# FIT_FPGA_G-H.net
KiCad netlist of a schematic drawn in Altium Designer
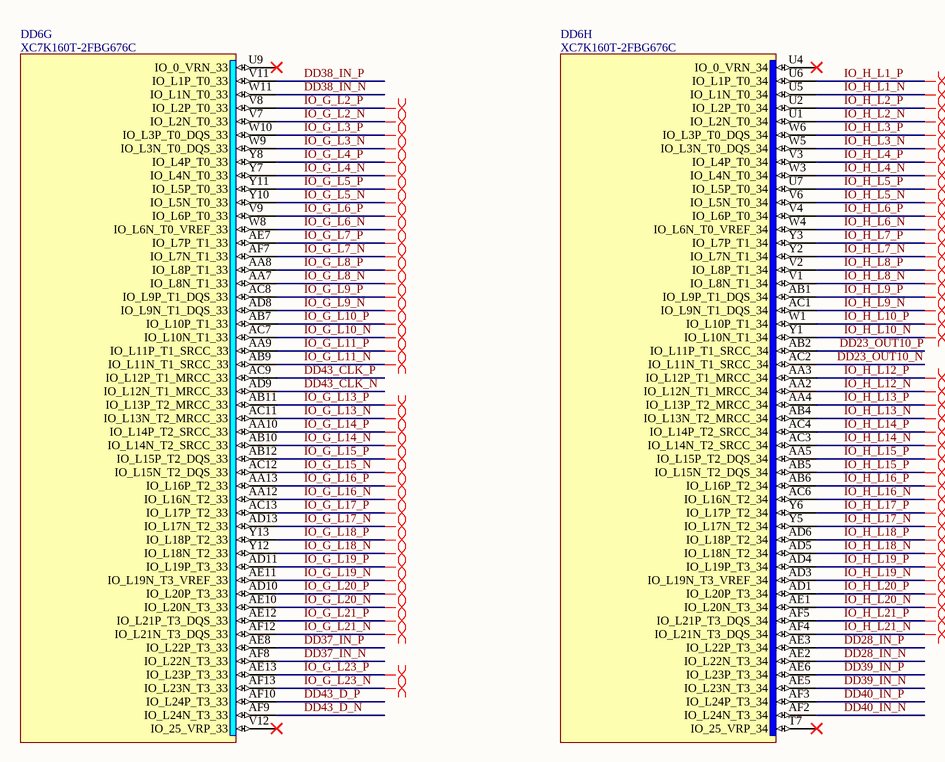
[diagram p0: FIT_FPGA_G-H.SchDoc]

(export (version "E")
  (design (tool "Eeschema 10.0.6"))
  (components
    (comp (ref "DD6")
      (value "XC7K160T-2FBG676C")
      (footprint "BGA676C100P26X26_2700X2700X254")
      (description "KINTEX-7, FPGA, 676-Ball BGA, Pb-Free")
      (fields (field (name "MANUFACTURER") "XILINX") (field (name "AUTHOR") "CERN DEM BC"))
      (libsource (lib "ICs And Semiconductors") (part "XC7K160T-xFBG676"))
    )
  )
  (nets
    (net (code "1") (name "/DD23_OUT10_N") (class "Default")
      (node (ref "DD6") (pin "AC2") (pinfunction "IO_L11N_T1_SRCC_34_AC2") (pintype "bidirectional"))
    )
    (net (code "2") (name "/DD23_OUT10_P") (class "Default")
      (node (ref "DD6") (pin "AB2") (pinfunction "IO_L11P_T1_SRCC_34_AB2") (pintype "bidirectional"))
    )
    (net (code "3") (name "/DD28_IN_N") (class "Default")
      (node (ref "DD6") (pin "AE2") (pinfunction "IO_L22N_T3_34_AE2") (pintype "bidirectional"))
    )
    (net (code "4") (name "/DD28_IN_P") (class "Default")
      (node (ref "DD6") (pin "AE3") (pinfunction "IO_L22P_T3_34_AE3") (pintype "bidirectional"))
    )
    (net (code "5") (name "/DD37_IN_N") (class "Default")
      (node (ref "DD6") (pin "AF8") (pinfunction "IO_L22N_T3_33_AF8") (pintype "bidirectional"))
    )
    (net (code "6") (name "/DD37_IN_P") (class "Default")
      (node (ref "DD6") (pin "AE8") (pinfunction "IO_L22P_T3_33_AE8") (pintype "bidirectional"))
    )
    (net (code "7") (name "/DD38_IN_N") (class "Default")
      (node (ref "DD6") (pin "W11") (pinfunction "IO_L1N_T0_33_W11") (pintype "bidirectional"))
    )
    (net (code "8") (name "/DD38_IN_P") (class "Default")
      (node (ref "DD6") (pin "V11") (pinfunction "IO_L1P_T0_33_V11") (pintype "bidirectional"))
    )
    (net (code "9") (name "/DD39_IN_N") (class "Default")
      (node (ref "DD6") (pin "AE5") (pinfunction "IO_L23N_T3_34_AE5") (pintype "bidirectional"))
    )
    (net (code "10") (name "/DD39_IN_P") (class "Default")
      (node (ref "DD6") (pin "AE6") (pinfunction "IO_L23P_T3_34_AE6") (pintype "bidirectional"))
    )
    (net (code "11") (name "/DD40_IN_N") (class "Default")
      (node (ref "DD6") (pin "AF2") (pinfunction "IO_L24N_T3_34_AF2") (pintype "bidirectional"))
    )
    (net (code "12") (name "/DD40_IN_P") (class "Default")
      (node (ref "DD6") (pin "AF3") (pinfunction "IO_L24P_T3_34_AF3") (pintype "bidirectional"))
    )
    (net (code "13") (name "/DD43_CLK_N") (class "Default")
      (node (ref "DD6") (pin "AD9") (pinfunction "IO_L12N_T1_MRCC_33_AD9") (pintype "bidirectional"))
    )
    (net (code "14") (name "/DD43_CLK_P") (class "Default")
      (node (ref "DD6") (pin "AC9") (pinfunction "IO_L12P_T1_MRCC_33_AC9") (pintype "bidirectional"))
    )
    (net (code "15") (name "/DD43_D_N") (class "Default")
      (node (ref "DD6") (pin "AF9") (pinfunction "IO_L24N_T3_33_AF9") (pintype "bidirectional"))
    )
    (net (code "16") (name "/DD43_D_P") (class "Default")
      (node (ref "DD6") (pin "AF10") (pinfunction "IO_L24P_T3_33_AF10") (pintype "bidirectional"))
    )
    (net (code "17") (name "/IO_G_L2_N") (class "Default")
      (node (ref "DD6") (pin "V7") (pinfunction "IO_L2N_T0_33_V7") (pintype "bidirectional"))
    )
    (net (code "18") (name "/IO_G_L2_P") (class "Default")
      (node (ref "DD6") (pin "V8") (pinfunction "IO_L2P_T0_33_V8") (pintype "bidirectional"))
    )
    (net (code "19") (name "/IO_G_L3_N") (class "Default")
      (node (ref "DD6") (pin "W9") (pinfunction "IO_L3N_T0_DQS_33_W9") (pintype "bidirectional"))
    )
    (net (code "20") (name "/IO_G_L3_P") (class "Default")
      (node (ref "DD6") (pin "W10") (pinfunction "IO_L3P_T0_DQS_33_W10") (pintype "bidirectional"))
    )
    (net (code "21") (name "/IO_G_L4_N") (class "Default")
      (node (ref "DD6") (pin "Y7") (pinfunction "IO_L4N_T0_33_Y7") (pintype "bidirectional"))
    )
    (net (code "22") (name "/IO_G_L4_P") (class "Default")
      (node (ref "DD6") (pin "Y8") (pinfunction "IO_L4P_T0_33_Y8") (pintype "bidirectional"))
    )
    (net (code "23") (name "/IO_G_L5_N") (class "Default")
      (node (ref "DD6") (pin "Y10") (pinfunction "IO_L5N_T0_33_Y10") (pintype "bidirectional"))
    )
    (net (code "24") (name "/IO_G_L5_P") (class "Default")
      (node (ref "DD6") (pin "Y11") (pinfunction "IO_L5P_T0_33_Y11") (pintype "bidirectional"))
    )
    (net (code "25") (name "/IO_G_L6_N") (class "Default")
      (node (ref "DD6") (pin "W8") (pinfunction "IO_L6N_T0_VREF_33_W8") (pintype "bidirectional"))
    )
    (net (code "26") (name "/IO_G_L6_P") (class "Default")
      (node (ref "DD6") (pin "V9") (pinfunction "IO_L6P_T0_33_V9") (pintype "bidirectional"))
    )
    (net (code "27") (name "/IO_G_L7_N") (class "Default")
      (node (ref "DD6") (pin "AF7") (pinfunction "IO_L7N_T1_33_AF7") (pintype "bidirectional"))
    )
    (net (code "28") (name "/IO_G_L7_P") (class "Default")
      (node (ref "DD6") (pin "AE7") (pinfunction "IO_L7P_T1_33_AE7") (pintype "bidirectional"))
    )
    (net (code "29") (name "/IO_G_L8_N") (class "Default")
      (node (ref "DD6") (pin "AA7") (pinfunction "IO_L8N_T1_33_AA7") (pintype "bidirectional"))
    )
    (net (code "30") (name "/IO_G_L8_P") (class "Default")
      (node (ref "DD6") (pin "AA8") (pinfunction "IO_L8P_T1_33_AA8") (pintype "bidirectional"))
    )
    (net (code "31") (name "/IO_G_L9_N") (class "Default")
      (node (ref "DD6") (pin "AD8") (pinfunction "IO_L9N_T1_DQS_33_AD8") (pintype "bidirectional"))
    )
    (net (code "32") (name "/IO_G_L9_P") (class "Default")
      (node (ref "DD6") (pin "AC8") (pinfunction "IO_L9P_T1_DQS_33_AC8") (pintype "bidirectional"))
    )
    (net (code "33") (name "/IO_G_L10_N") (class "Default")
      (node (ref "DD6") (pin "AC7") (pinfunction "IO_L10N_T1_33_AC7") (pintype "bidirectional"))
    )
    (net (code "34") (name "/IO_G_L10_P") (class "Default")
      (node (ref "DD6") (pin "AB7") (pinfunction "IO_L10P_T1_33_AB7") (pintype "bidirectional"))
    )
    (net (code "35") (name "/IO_G_L11_N") (class "Default")
      (node (ref "DD6") (pin "AB9") (pinfunction "IO_L11N_T1_SRCC_33_AB9") (pintype "bidirectional"))
    )
    (net (code "36") (name "/IO_G_L11_P") (class "Default")
      (node (ref "DD6") (pin "AA9") (pinfunction "IO_L11P_T1_SRCC_33_AA9") (pintype "bidirectional"))
    )
    (net (code "37") (name "/IO_G_L13_N") (class "Default")
      (node (ref "DD6") (pin "AC11") (pinfunction "IO_L13N_T2_MRCC_33_AC11") (pintype "bidirectional"))
    )
    (net (code "38") (name "/IO_G_L13_P") (class "Default")
      (node (ref "DD6") (pin "AB11") (pinfunction "IO_L13P_T2_MRCC_33_AB11") (pintype "bidirectional"))
    )
    (net (code "39") (name "/IO_G_L14_N") (class "Default")
      (node (ref "DD6") (pin "AB10") (pinfunction "IO_L14N_T2_SRCC_33_AB10") (pintype "bidirectional"))
    )
    (net (code "40") (name "/IO_G_L14_P") (class "Default")
      (node (ref "DD6") (pin "AA10") (pinfunction "IO_L14P_T2_SRCC_33_AA10") (pintype "bidirectional"))
    )
    (net (code "41") (name "/IO_G_L15_N") (class "Default")
      (node (ref "DD6") (pin "AC12") (pinfunction "IO_L15N_T2_DQS_33_AC12") (pintype "bidirectional"))
    )
    (net (code "42") (name "/IO_G_L15_P") (class "Default")
      (node (ref "DD6") (pin "AB12") (pinfunction "IO_L15P_T2_DQS_33_AB12") (pintype "bidirectional"))
    )
    (net (code "43") (name "/IO_G_L16_N") (class "Default")
      (node (ref "DD6") (pin "AA12") (pinfunction "IO_L16N_T2_33_AA12") (pintype "bidirectional"))
    )
    (net (code "44") (name "/IO_G_L16_P") (class "Default")
      (node (ref "DD6") (pin "AA13") (pinfunction "IO_L16P_T2_33_AA13") (pintype "bidirectional"))
    )
    (net (code "45") (name "/IO_G_L17_N") (class "Default")
      (node (ref "DD6") (pin "AD13") (pinfunction "IO_L17N_T2_33_AD13") (pintype "bidirectional"))
    )
    (net (code "46") (name "/IO_G_L17_P") (class "Default")
      (node (ref "DD6") (pin "AC13") (pinfunction "IO_L17P_T2_33_AC13") (pintype "bidirectional"))
    )
    (net (code "47") (name "/IO_G_L18_N") (class "Default")
      (node (ref "DD6") (pin "Y12") (pinfunction "IO_L18N_T2_33_Y12") (pintype "bidirectional"))
    )
    (net (code "48") (name "/IO_G_L18_P") (class "Default")
      (node (ref "DD6") (pin "Y13") (pinfunction "IO_L18P_T2_33_Y13") (pintype "bidirectional"))
    )
    (net (code "49") (name "/IO_G_L19_N") (class "Default")
      (node (ref "DD6") (pin "AE11") (pinfunction "IO_L19N_T3_VREF_33_AE11") (pintype "bidirectional"))
    )
    (net (code "50") (name "/IO_G_L19_P") (class "Default")
      (node (ref "DD6") (pin "AD11") (pinfunction "IO_L19P_T3_33_AD11") (pintype "bidirectional"))
    )
    (net (code "51") (name "/IO_G_L20_N") (class "Default")
      (node (ref "DD6") (pin "AE10") (pinfunction "IO_L20N_T3_33_AE10") (pintype "bidirectional"))
    )
    (net (code "52") (name "/IO_G_L20_P") (class "Default")
      (node (ref "DD6") (pin "AD10") (pinfunction "IO_L20P_T3_33_AD10") (pintype "bidirectional"))
    )
    (net (code "53") (name "/IO_G_L21_N") (class "Default")
      (node (ref "DD6") (pin "AF12") (pinfunction "IO_L21N_T3_DQS_33_AF12") (pintype "bidirectional"))
    )
    (net (code "54") (name "/IO_G_L21_P") (class "Default")
      (node (ref "DD6") (pin "AE12") (pinfunction "IO_L21P_T3_DQS_33_AE12") (pintype "bidirectional"))
    )
    (net (code "55") (name "/IO_G_L23_N") (class "Default")
      (node (ref "DD6") (pin "AF13") (pinfunction "IO_L23N_T3_33_AF13") (pintype "bidirectional"))
    )
    (net (code "56") (name "/IO_G_L23_P") (class "Default")
      (node (ref "DD6") (pin "AE13") (pinfunction "IO_L23P_T3_33_AE13") (pintype "bidirectional"))
    )
    (net (code "57") (name "/IO_H_L1_N") (class "Default")
      (node (ref "DD6") (pin "U5") (pinfunction "IO_L1N_T0_34_U5") (pintype "bidirectional"))
    )
    (net (code "58") (name "/IO_H_L1_P") (class "Default")
      (node (ref "DD6") (pin "U6") (pinfunction "IO_L1P_T0_34_U6") (pintype "bidirectional"))
    )
    (net (code "59") (name "/IO_H_L2_N") (class "Default")
      (node (ref "DD6") (pin "U1") (pinfunction "IO_L2N_T0_34_U1") (pintype "bidirectional"))
    )
    (net (code "60") (name "/IO_H_L2_P") (class "Default")
      (node (ref "DD6") (pin "U2") (pinfunction "IO_L2P_T0_34_U2") (pintype "bidirectional"))
    )
    (net (code "61") (name "/IO_H_L3_N") (class "Default")
      (node (ref "DD6") (pin "W5") (pinfunction "IO_L3N_T0_DQS_34_W5") (pintype "bidirectional"))
    )
    (net (code "62") (name "/IO_H_L3_P") (class "Default")
      (node (ref "DD6") (pin "W6") (pinfunction "IO_L3P_T0_DQS_34_W6") (pintype "bidirectional"))
    )
    (net (code "63") (name "/IO_H_L4_N") (class "Default")
      (node (ref "DD6") (pin "W3") (pinfunction "IO_L4N_T0_34_W3") (pintype "bidirectional"))
    )
    (net (code "64") (name "/IO_H_L4_P") (class "Default")
      (node (ref "DD6") (pin "V3") (pinfunction "IO_L4P_T0_34_V3") (pintype "bidirectional"))
    )
    (net (code "65") (name "/IO_H_L5_N") (class "Default")
      (node (ref "DD6") (pin "V6") (pinfunction "IO_L5N_T0_34_V6") (pintype "bidirectional"))
    )
    (net (code "66") (name "/IO_H_L5_P") (class "Default")
      (node (ref "DD6") (pin "U7") (pinfunction "IO_L5P_T0_34_U7") (pintype "bidirectional"))
    )
    (net (code "67") (name "/IO_H_L6_N") (class "Default")
      (node (ref "DD6") (pin "W4") (pinfunction "IO_L6N_T0_VREF_34_W4") (pintype "bidirectional"))
    )
    (net (code "68") (name "/IO_H_L6_P") (class "Default")
      (node (ref "DD6") (pin "V4") (pinfunction "IO_L6P_T0_34_V4") (pintype "bidirectional"))
    )
    (net (code "69") (name "/IO_H_L7_N") (class "Default")
      (node (ref "DD6") (pin "Y2") (pinfunction "IO_L7N_T1_34_Y2") (pintype "bidirectional"))
    )
    (net (code "70") (name "/IO_H_L7_P") (class "Default")
      (node (ref "DD6") (pin "Y3") (pinfunction "IO_L7P_T1_34_Y3") (pintype "bidirectional"))
    )
    (net (code "71") (name "/IO_H_L8_N") (class "Default")
      (node (ref "DD6") (pin "V1") (pinfunction "IO_L8N_T1_34_V1") (pintype "bidirectional"))
    )
    (net (code "72") (name "/IO_H_L8_P") (class "Default")
      (node (ref "DD6") (pin "V2") (pinfunction "IO_L8P_T1_34_V2") (pintype "bidirectional"))
    )
    (net (code "73") (name "/IO_H_L9_N") (class "Default")
      (node (ref "DD6") (pin "AC1") (pinfunction "IO_L9N_T1_DQS_34_AC1") (pintype "bidirectional"))
    )
    (net (code "74") (name "/IO_H_L9_P") (class "Default")
      (node (ref "DD6") (pin "AB1") (pinfunction "IO_L9P_T1_DQS_34_AB1") (pintype "bidirectional"))
    )
    (net (code "75") (name "/IO_H_L10_N") (class "Default")
      (node (ref "DD6") (pin "Y1") (pinfunction "IO_L10N_T1_34_Y1") (pintype "bidirectional"))
    )
    (net (code "76") (name "/IO_H_L10_P") (class "Default")
      (node (ref "DD6") (pin "W1") (pinfunction "IO_L10P_T1_34_W1") (pintype "bidirectional"))
    )
    (net (code "77") (name "/IO_H_L12_N") (class "Default")
      (node (ref "DD6") (pin "AA2") (pinfunction "IO_L12N_T1_MRCC_34_AA2") (pintype "bidirectional"))
    )
    (net (code "78") (name "/IO_H_L12_P") (class "Default")
      (node (ref "DD6") (pin "AA3") (pinfunction "IO_L12P_T1_MRCC_34_AA3") (pintype "bidirectional"))
    )
    (net (code "79") (name "/IO_H_L13_N") (class "Default")
      (node (ref "DD6") (pin "AB4") (pinfunction "IO_L13N_T2_MRCC_34_AB4") (pintype "bidirectional"))
    )
    (net (code "80") (name "/IO_H_L13_P") (class "Default")
      (node (ref "DD6") (pin "AA4") (pinfunction "IO_L13P_T2_MRCC_34_AA4") (pintype "bidirectional"))
    )
    (net (code "81") (name "/IO_H_L14_N") (class "Default")
      (node (ref "DD6") (pin "AC3") (pinfunction "IO_L14N_T2_SRCC_34_AC3") (pintype "bidirectional"))
    )
    (net (code "82") (name "/IO_H_L14_P") (class "Default")
      (node (ref "DD6") (pin "AC4") (pinfunction "IO_L14P_T2_SRCC_34_AC4") (pintype "bidirectional"))
    )
    (net (code "83") (name "/IO_H_L15_P") (class "Default")
      (node (ref "DD6") (pin "AA5") (pinfunction "IO_L15P_T2_DQS_34_AA5") (pintype "bidirectional"))
      (node (ref "DD6") (pin "AB5") (pinfunction "IO_L15N_T2_DQS_34_AB5") (pintype "bidirectional"))
    )
    (net (code "84") (name "/IO_H_L16_N") (class "Default")
      (node (ref "DD6") (pin "AC6") (pinfunction "IO_L16N_T2_34_AC6") (pintype "bidirectional"))
    )
    (net (code "85") (name "/IO_H_L16_P") (class "Default")
      (node (ref "DD6") (pin "AB6") (pinfunction "IO_L16P_T2_34_AB6") (pintype "bidirectional"))
    )
    (net (code "86") (name "/IO_H_L17_N") (class "Default")
      (node (ref "DD6") (pin "Y5") (pinfunction "IO_L17N_T2_34_Y5") (pintype "bidirectional"))
    )
    (net (code "87") (name "/IO_H_L17_P") (class "Default")
      (node (ref "DD6") (pin "Y6") (pinfunction "IO_L17P_T2_34_Y6") (pintype "bidirectional"))
    )
    (net (code "88") (name "/IO_H_L18_N") (class "Default")
      (node (ref "DD6") (pin "AD5") (pinfunction "IO_L18N_T2_34_AD5") (pintype "bidirectional"))
    )
    (net (code "89") (name "/IO_H_L18_P") (class "Default")
      (node (ref "DD6") (pin "AD6") (pinfunction "IO_L18P_T2_34_AD6") (pintype "bidirectional"))
    )
    (net (code "90") (name "/IO_H_L19_N") (class "Default")
      (node (ref "DD6") (pin "AD3") (pinfunction "IO_L19N_T3_VREF_34_AD3") (pintype "bidirectional"))
    )
    (net (code "91") (name "/IO_H_L19_P") (class "Default")
      (node (ref "DD6") (pin "AD4") (pinfunction "IO_L19P_T3_34_AD4") (pintype "bidirectional"))
    )
    (net (code "92") (name "/IO_H_L20_N") (class "Default")
      (node (ref "DD6") (pin "AE1") (pinfunction "IO_L20N_T3_34_AE1") (pintype "bidirectional"))
    )
    (net (code "93") (name "/IO_H_L20_P") (class "Default")
      (node (ref "DD6") (pin "AD1") (pinfunction "IO_L20P_T3_34_AD1") (pintype "bidirectional"))
    )
    (net (code "94") (name "/IO_H_L21_N") (class "Default")
      (node (ref "DD6") (pin "AF4") (pinfunction "IO_L21N_T3_DQS_34_AF4") (pintype "bidirectional"))
    )
    (net (code "95") (name "/IO_H_L21_P") (class "Default")
      (node (ref "DD6") (pin "AF5") (pinfunction "IO_L21P_T3_DQS_34_AF5") (pintype "bidirectional"))
    )
    (net (code "96") (name "unconnected-(DD6G-IO_0_VRN_33-PadU9)") (class "Default")
      (node (ref "DD6") (pin "U9") (pinfunction "IO_0_VRN_33_U9") (pintype "bidirectional+no_connect"))
    )
    (net (code "97") (name "unconnected-(DD6G-IO_25_VRP_33-PadV12)") (class "Default")
      (node (ref "DD6") (pin "V12") (pinfunction "IO_25_VRP_33_V12") (pintype "bidirectional+no_connect"))
    )
    (net (code "98") (name "unconnected-(DD6H-IO_0_VRN_34-PadU4)") (class "Default")
      (node (ref "DD6") (pin "U4") (pinfunction "IO_0_VRN_34_U4") (pintype "bidirectional+no_connect"))
    )
    (net (code "99") (name "unconnected-(DD6H-IO_25_VRP_34-PadT7)") (class "Default")
      (node (ref "DD6") (pin "T7") (pinfunction "IO_25_VRP_34_T7") (pintype "bidirectional+no_connect"))
    )
  )
)
